# Output.net
KiCad netlist of a schematic drawn in Altium Designer
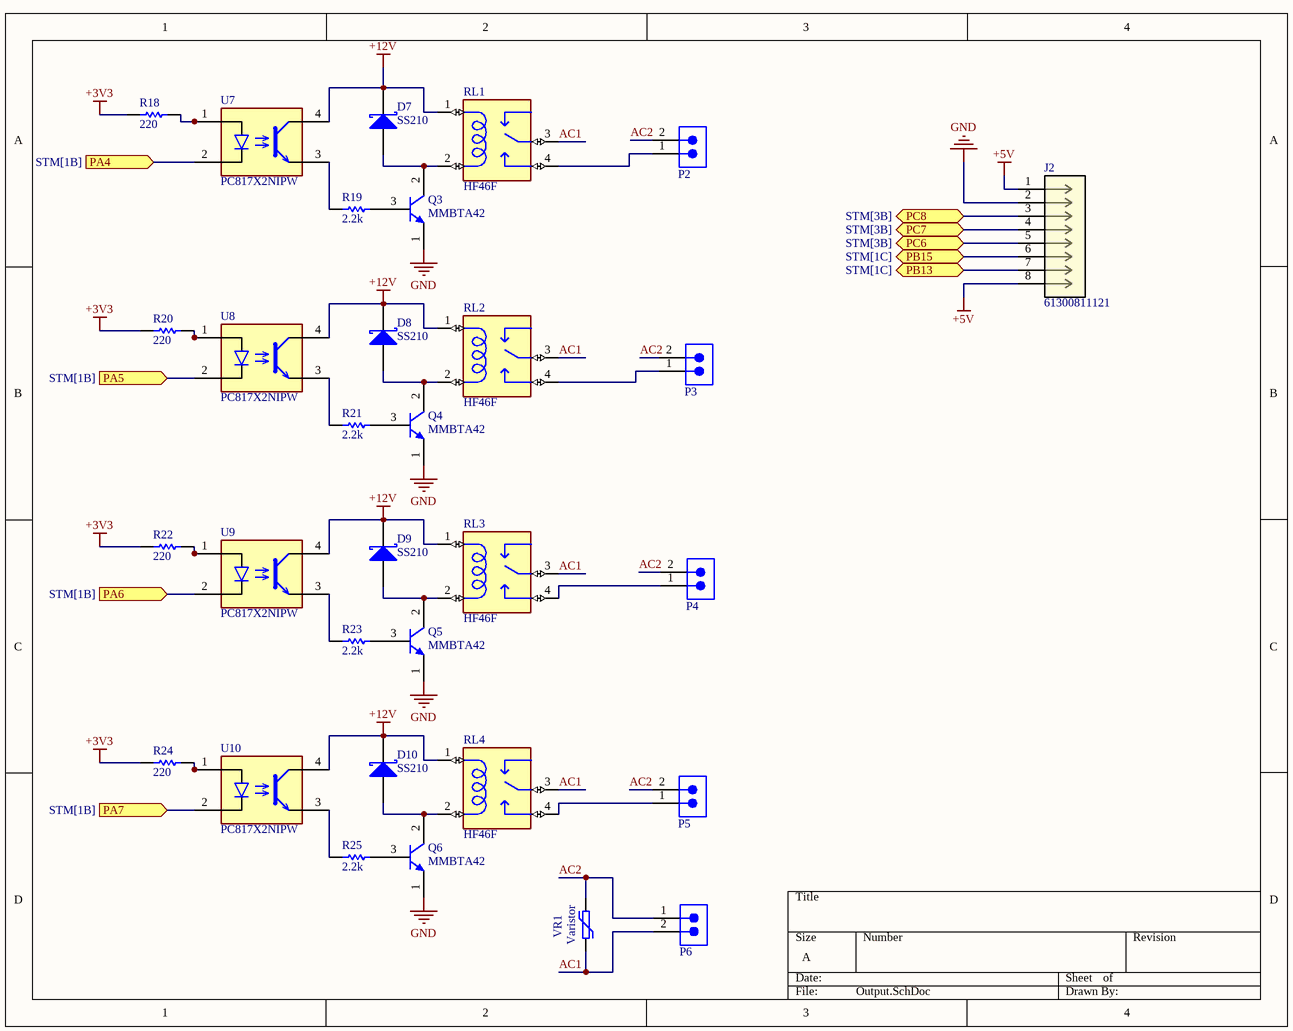
[diagram p0: Output.SchDoc]

(export (version "E")
  (design (tool "Eeschema 10.0.6"))
  (components
    (comp (ref "D7")
      (value "SS210")
      (footprint "SS34")
      (description "Schottky Diode")
      (fields (field (name "PUBLISHER") "Altium Limited"))
      (libsource (lib "SMIOT_Lib_Schematic") (part "D Schottky"))
    )
    (comp (ref "D8")
      (value "SS210")
      (footprint "SS34")
      (description "Schottky Diode")
      (fields (field (name "PUBLISHER") "Altium Limited"))
      (libsource (lib "SMIOT_Lib_Schematic") (part "D Schottky"))
    )
    (comp (ref "D9")
      (value "SS210")
      (footprint "SS34")
      (description "Schottky Diode")
      (fields (field (name "PUBLISHER") "Altium Limited"))
      (libsource (lib "SMIOT_Lib_Schematic") (part "D Schottky"))
    )
    (comp (ref "D10")
      (value "SS210")
      (footprint "SS34")
      (description "Schottky Diode")
      (fields (field (name "PUBLISHER") "Altium Limited"))
      (libsource (lib "SMIOT_Lib_Schematic") (part "D Schottky"))
    )
    (comp (ref "J2")
      (value "61300811121")
      (footprint "CONN8_61300811121_WRE")
      (description "No Description Available")
      (libsource (lib "61300811121") (part "61300811121"))
    )
    (comp (ref "P2")
      (value "691322310002")
      (footprint "691322310002")
      (description "WR-TBL Series 322 Horizontal PCB Header, THT, pitch 3.81mm, 2p")
      (fields (field (name "MANUFACTURER") "Wurth Elektronik"))
      (libsource (lib "SMIOT_Lib_Schematic") (part "691322310002"))
    )
    (comp (ref "P3")
      (value "691322310002")
      (footprint "691322310002")
      (description "WR-TBL Series 322 Horizontal PCB Header, THT, pitch 3.81mm, 2p")
      (fields (field (name "MANUFACTURER") "Wurth Elektronik"))
      (libsource (lib "SMIOT_Lib_Schematic") (part "691322310002"))
    )
    (comp (ref "P4")
      (value "691322310002")
      (footprint "691322310002")
      (description "WR-TBL Series 322 Horizontal PCB Header, THT, pitch 3.81mm, 2p")
      (fields (field (name "MANUFACTURER") "Wurth Elektronik"))
      (libsource (lib "SMIOT_Lib_Schematic") (part "691322310002"))
    )
    (comp (ref "P5")
      (value "691322310002")
      (footprint "691322310002")
      (description "WR-TBL Series 322 Horizontal PCB Header, THT, pitch 3.81mm, 2p")
      (fields (field (name "MANUFACTURER") "Wurth Elektronik"))
      (libsource (lib "SMIOT_Lib_Schematic") (part "691322310002"))
    )
    (comp (ref "P6")
      (value "691322310002")
      (footprint "691322310002")
      (description "WR-TBL Series 322 Horizontal PCB Header, THT, pitch 3.81mm, 2p")
      (fields (field (name "MANUFACTURER") "Wurth Elektronik"))
      (libsource (lib "SMIOT_Lib_Schematic") (part "691322310002"))
    )
    (comp (ref "Q3")
      (value "MMBTA42")
      (footprint "SOT23B")
      (description "NPN Bipolar Transistor")
      (libsource (lib "SMIOT_Lib_Schematic") (part "BC817"))
    )
    (comp (ref "Q4")
      (value "MMBTA42")
      (footprint "SOT23B")
      (description "NPN Bipolar Transistor")
      (libsource (lib "SMIOT_Lib_Schematic") (part "BC817"))
    )
    (comp (ref "Q5")
      (value "MMBTA42")
      (footprint "SOT23B")
      (description "NPN Bipolar Transistor")
      (libsource (lib "SMIOT_Lib_Schematic") (part "BC817"))
    )
    (comp (ref "Q6")
      (value "MMBTA42")
      (footprint "SOT23B")
      (description "NPN Bipolar Transistor")
      (libsource (lib "SMIOT_Lib_Schematic") (part "BC817"))
    )
    (comp (ref "R18")
      (value "220")
      (footprint "resistor_0603")
      (description "RES, 220 Ohm, size 0603, 1%")
      (libsource (lib "SMIOT_Lib_Schematic") (part "0006032211"))
    )
    (comp (ref "R19")
      (value "2.2k")
      (footprint "resistor_0603")
      (description "RES, 2.2k Ohm, size 0603, 1%")
      (libsource (lib "SMIOT_Lib_Schematic") (part "0006032221"))
    )
    (comp (ref "R20")
      (value "220")
      (footprint "resistor_0603")
      (description "RES, 220 Ohm, size 0603, 1%")
      (libsource (lib "SMIOT_Lib_Schematic") (part "0006032211"))
    )
    (comp (ref "R21")
      (value "2.2k")
      (footprint "resistor_0603")
      (description "RES, 2.2k Ohm, size 0603, 1%")
      (libsource (lib "SMIOT_Lib_Schematic") (part "0006032221"))
    )
    (comp (ref "R22")
      (value "220")
      (footprint "resistor_0603")
      (description "RES, 220 Ohm, size 0603, 1%")
      (libsource (lib "SMIOT_Lib_Schematic") (part "0006032211"))
    )
    (comp (ref "R23")
      (value "2.2k")
      (footprint "resistor_0603")
      (description "RES, 2.2k Ohm, size 0603, 1%")
      (libsource (lib "SMIOT_Lib_Schematic") (part "0006032221"))
    )
    (comp (ref "R24")
      (value "220")
      (footprint "resistor_0603")
      (description "RES, 220 Ohm, size 0603, 1%")
      (libsource (lib "SMIOT_Lib_Schematic") (part "0006032211"))
    )
    (comp (ref "R25")
      (value "2.2k")
      (footprint "resistor_0603")
      (description "RES, 2.2k Ohm, size 0603, 1%")
      (libsource (lib "SMIOT_Lib_Schematic") (part "0006032221"))
    )
    (comp (ref "RL1")
      (value "HF46F")
      (footprint "HF46F")
      (description "SeriesHF46F 12V 1 Form A 1A Gold Plated SUBMINIATURE INTERMEDIATE POWER RELAY")
      (fields (field (name "MF") "Hongfa"))
      (libsource (lib "SMIOT_Lib_Schematic") (part "HF46F"))
    )
    (comp (ref "RL2")
      (value "HF46F")
      (footprint "HF46F")
      (description "SeriesHF46F 12V 1 Form A 1A Gold Plated SUBMINIATURE INTERMEDIATE POWER RELAY")
      (fields (field (name "MF") "Hongfa"))
      (libsource (lib "SMIOT_Lib_Schematic") (part "HF46F"))
    )
    (comp (ref "RL3")
      (value "HF46F")
      (footprint "HF46F")
      (description "SeriesHF46F 12V 1 Form A 1A Gold Plated SUBMINIATURE INTERMEDIATE POWER RELAY")
      (fields (field (name "MF") "Hongfa"))
      (libsource (lib "SMIOT_Lib_Schematic") (part "HF46F"))
    )
    (comp (ref "RL4")
      (value "HF46F")
      (footprint "HF46F")
      (description "SeriesHF46F 12V 1 Form A 1A Gold Plated SUBMINIATURE INTERMEDIATE POWER RELAY")
      (fields (field (name "MF") "Hongfa"))
      (libsource (lib "SMIOT_Lib_Schematic") (part "HF46F"))
    )
    (comp (ref "U7")
      (value "PC817X2NIPW")
      (footprint "PC817XI_SHP")
      (libsource (lib "SMIOT_Lib_Schematic") (part "PC817X2NIPW"))
    )
    (comp (ref "U8")
      (value "PC817X2NIPW")
      (footprint "PC817XI_SHP")
      (libsource (lib "SMIOT_Lib_Schematic") (part "PC817X2NIPW"))
    )
    (comp (ref "U9")
      (value "PC817X2NIPW")
      (footprint "PC817XI_SHP")
      (libsource (lib "SMIOT_Lib_Schematic") (part "PC817X2NIPW"))
    )
    (comp (ref "U10")
      (value "PC817X2NIPW")
      (footprint "PC817XI_SHP")
      (libsource (lib "SMIOT_Lib_Schematic") (part "PC817X2NIPW"))
    )
    (comp (ref "VR1")
      (value "Varistor")
      (footprint "07D471K")
      (description "07D471K 470V")
      (libsource (lib "SMIOT_Lib_Schematic") (part "07D471K 470V"))
    )
  )
  (nets
    (net (code "1") (name "+3V3") (class "Default")
      (node (ref "R18") (pin "1") (pinfunction "1_1") (pintype "passive"))
      (node (ref "R20") (pin "1") (pinfunction "1_1") (pintype "passive"))
      (node (ref "R22") (pin "1") (pinfunction "1_1") (pintype "passive"))
      (node (ref "R24") (pin "1") (pinfunction "1_1") (pintype "passive"))
    )
    (net (code "2") (name "+5V") (class "Default")
      (node (ref "J2") (pin "1") (pinfunction "1_1") (pintype "passive"))
      (node (ref "J2") (pin "8") (pinfunction "8_8") (pintype "passive"))
    )
    (net (code "3") (name "+12V") (class "Default")
      (node (ref "D10") (pin "2") (pinfunction "K_2") (pintype "passive"))
      (node (ref "D7") (pin "2") (pinfunction "K_2") (pintype "passive"))
      (node (ref "D8") (pin "2") (pinfunction "K_2") (pintype "passive"))
      (node (ref "D9") (pin "2") (pinfunction "K_2") (pintype "passive"))
      (node (ref "RL1") (pin "1") (pinfunction "C1_1") (pintype "bidirectional"))
      (node (ref "RL2") (pin "1") (pinfunction "C1_1") (pintype "bidirectional"))
      (node (ref "RL3") (pin "1") (pinfunction "C1_1") (pintype "bidirectional"))
      (node (ref "RL4") (pin "1") (pinfunction "C1_1") (pintype "bidirectional"))
      (node (ref "U10") (pin "4") (pinfunction "4_4") (pintype "passive"))
      (node (ref "U7") (pin "4") (pinfunction "4_4") (pintype "passive"))
      (node (ref "U8") (pin "4") (pinfunction "4_4") (pintype "passive"))
      (node (ref "U9") (pin "4") (pinfunction "4_4") (pintype "passive"))
    )
    (net (code "4") (name "/AC1") (class "Default")
      (node (ref "P6") (pin "2") (pinfunction "2_2") (pintype "passive"))
      (node (ref "RL1") (pin "3") (pinfunction "C_3") (pintype "bidirectional"))
      (node (ref "RL2") (pin "3") (pinfunction "C_3") (pintype "bidirectional"))
      (node (ref "RL3") (pin "3") (pinfunction "C_3") (pintype "bidirectional"))
      (node (ref "RL4") (pin "3") (pinfunction "C_3") (pintype "bidirectional"))
      (node (ref "VR1") (pin "2") (pinfunction "2_2") (pintype "passive"))
    )
    (net (code "5") (name "/AC2") (class "Default")
      (node (ref "P2") (pin "2") (pinfunction "2_2") (pintype "passive"))
      (node (ref "P3") (pin "2") (pinfunction "2_2") (pintype "passive"))
      (node (ref "P4") (pin "2") (pinfunction "2_2") (pintype "passive"))
      (node (ref "P5") (pin "2") (pinfunction "2_2") (pintype "passive"))
      (node (ref "P6") (pin "1") (pinfunction "1_1") (pintype "passive"))
      (node (ref "VR1") (pin "1") (pinfunction "1_1") (pintype "passive"))
    )
    (net (code "6") (name "/PA4") (class "Default")
      (node (ref "U7") (pin "2") (pinfunction "2_2") (pintype "passive"))
    )
    (net (code "7") (name "/PA5") (class "Default")
      (node (ref "U8") (pin "2") (pinfunction "2_2") (pintype "passive"))
    )
    (net (code "8") (name "/PA6") (class "Default")
      (node (ref "U9") (pin "2") (pinfunction "2_2") (pintype "passive"))
    )
    (net (code "9") (name "/PA7") (class "Default")
      (node (ref "U10") (pin "2") (pinfunction "2_2") (pintype "passive"))
    )
    (net (code "10") (name "/PB13") (class "Default")
      (node (ref "J2") (pin "7") (pinfunction "7_7") (pintype "passive"))
    )
    (net (code "11") (name "/PB15") (class "Default")
      (node (ref "J2") (pin "6") (pinfunction "6_6") (pintype "passive"))
    )
    (net (code "12") (name "/PC6") (class "Default")
      (node (ref "J2") (pin "5") (pinfunction "5_5") (pintype "passive"))
    )
    (net (code "13") (name "/PC7") (class "Default")
      (node (ref "J2") (pin "4") (pinfunction "4_4") (pintype "passive"))
    )
    (net (code "14") (name "/PC8") (class "Default")
      (node (ref "J2") (pin "3") (pinfunction "3_3") (pintype "passive"))
    )
    (net (code "15") (name "GND") (class "Default")
      (node (ref "J2") (pin "2") (pinfunction "2_2") (pintype "passive"))
      (node (ref "Q3") (pin "1") (pinfunction "E_1") (pintype "passive"))
      (node (ref "Q4") (pin "1") (pinfunction "E_1") (pintype "passive"))
      (node (ref "Q5") (pin "1") (pinfunction "E_1") (pintype "passive"))
      (node (ref "Q6") (pin "1") (pinfunction "E_1") (pintype "passive"))
    )
    (net (code "16") (name "Net-(D7-A)") (class "Default")
      (node (ref "D7") (pin "1") (pinfunction "A_1") (pintype "passive"))
      (node (ref "Q3") (pin "2") (pinfunction "C_2") (pintype "passive"))
      (node (ref "RL1") (pin "2") (pinfunction "C2_2") (pintype "bidirectional"))
    )
    (net (code "17") (name "Net-(D8-A)") (class "Default")
      (node (ref "D8") (pin "1") (pinfunction "A_1") (pintype "passive"))
      (node (ref "Q4") (pin "2") (pinfunction "C_2") (pintype "passive"))
      (node (ref "RL2") (pin "2") (pinfunction "C2_2") (pintype "bidirectional"))
    )
    (net (code "18") (name "Net-(D9-A)") (class "Default")
      (node (ref "D9") (pin "1") (pinfunction "A_1") (pintype "passive"))
      (node (ref "Q5") (pin "2") (pinfunction "C_2") (pintype "passive"))
      (node (ref "RL3") (pin "2") (pinfunction "C2_2") (pintype "bidirectional"))
    )
    (net (code "19") (name "Net-(D10-A)") (class "Default")
      (node (ref "D10") (pin "1") (pinfunction "A_1") (pintype "passive"))
      (node (ref "Q6") (pin "2") (pinfunction "C_2") (pintype "passive"))
      (node (ref "RL4") (pin "2") (pinfunction "C2_2") (pintype "bidirectional"))
    )
    (net (code "20") (name "Net-(Q3-B)") (class "Default")
      (node (ref "Q3") (pin "3") (pinfunction "B_3") (pintype "passive"))
      (node (ref "R19") (pin "2") (pinfunction "2_2") (pintype "passive"))
    )
    (net (code "21") (name "Net-(Q4-B)") (class "Default")
      (node (ref "Q4") (pin "3") (pinfunction "B_3") (pintype "passive"))
      (node (ref "R21") (pin "2") (pinfunction "2_2") (pintype "passive"))
    )
    (net (code "22") (name "Net-(Q5-B)") (class "Default")
      (node (ref "Q5") (pin "3") (pinfunction "B_3") (pintype "passive"))
      (node (ref "R23") (pin "2") (pinfunction "2_2") (pintype "passive"))
    )
    (net (code "23") (name "Net-(Q6-B)") (class "Default")
      (node (ref "Q6") (pin "3") (pinfunction "B_3") (pintype "passive"))
      (node (ref "R25") (pin "2") (pinfunction "2_2") (pintype "passive"))
    )
    (net (code "24") (name "Net-(R18-Pad2)") (class "Default")
      (node (ref "R18") (pin "2") (pinfunction "2_2") (pintype "passive"))
      (node (ref "U7") (pin "1") (pinfunction "1_1") (pintype "passive"))
    )
    (net (code "25") (name "Net-(R19-Pad1)") (class "Default")
      (node (ref "R19") (pin "1") (pinfunction "1_1") (pintype "passive"))
      (node (ref "U7") (pin "3") (pinfunction "3_3") (pintype "passive"))
    )
    (net (code "26") (name "Net-(R20-Pad2)") (class "Default")
      (node (ref "R20") (pin "2") (pinfunction "2_2") (pintype "passive"))
      (node (ref "U8") (pin "1") (pinfunction "1_1") (pintype "passive"))
    )
    (net (code "27") (name "Net-(R21-Pad1)") (class "Default")
      (node (ref "R21") (pin "1") (pinfunction "1_1") (pintype "passive"))
      (node (ref "U8") (pin "3") (pinfunction "3_3") (pintype "passive"))
    )
    (net (code "28") (name "Net-(R22-Pad2)") (class "Default")
      (node (ref "R22") (pin "2") (pinfunction "2_2") (pintype "passive"))
      (node (ref "U9") (pin "1") (pinfunction "1_1") (pintype "passive"))
    )
    (net (code "29") (name "Net-(R23-Pad1)") (class "Default")
      (node (ref "R23") (pin "1") (pinfunction "1_1") (pintype "passive"))
      (node (ref "U9") (pin "3") (pinfunction "3_3") (pintype "passive"))
    )
    (net (code "30") (name "Net-(R24-Pad2)") (class "Default")
      (node (ref "R24") (pin "2") (pinfunction "2_2") (pintype "passive"))
      (node (ref "U10") (pin "1") (pinfunction "1_1") (pintype "passive"))
    )
    (net (code "31") (name "Net-(R25-Pad1)") (class "Default")
      (node (ref "R25") (pin "1") (pinfunction "1_1") (pintype "passive"))
      (node (ref "U10") (pin "3") (pinfunction "3_3") (pintype "passive"))
    )
    (net (code "32") (name "Net-(RL1-NO)") (class "Default")
      (node (ref "P2") (pin "1") (pinfunction "1_1") (pintype "passive"))
      (node (ref "RL1") (pin "4") (pinfunction "NO_4") (pintype "bidirectional"))
    )
    (net (code "33") (name "Net-(RL2-NO)") (class "Default")
      (node (ref "P3") (pin "1") (pinfunction "1_1") (pintype "passive"))
      (node (ref "RL2") (pin "4") (pinfunction "NO_4") (pintype "bidirectional"))
    )
    (net (code "34") (name "Net-(RL3-NO)") (class "Default")
      (node (ref "P4") (pin "1") (pinfunction "1_1") (pintype "passive"))
      (node (ref "RL3") (pin "4") (pinfunction "NO_4") (pintype "bidirectional"))
    )
    (net (code "35") (name "Net-(RL4-NO)") (class "Default")
      (node (ref "P5") (pin "1") (pinfunction "1_1") (pintype "passive"))
      (node (ref "RL4") (pin "4") (pinfunction "NO_4") (pintype "bidirectional"))
    )
  )
)
